# EMP31.net
KiCad netlist of a schematic drawn in EAGLE
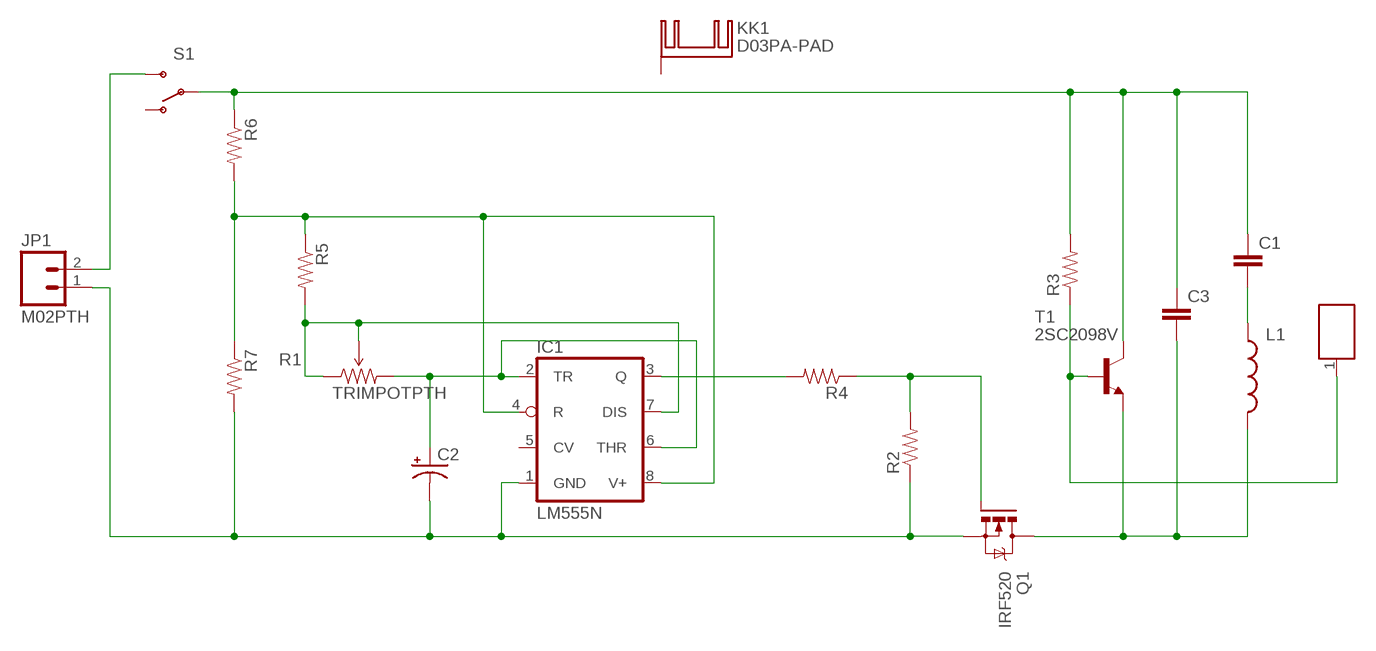
[diagram p0: schematic, sheet 1]

(export (version "E")
  (design (tool "Eeschema 10.0.6"))
  (components
    (comp (ref "C1")
      (value "CAPEZ")
      (footprint "eagle-import:CAP-PTH-SMALLEZ")
      (libsource (lib "eagle-import") (part "CAPEZ"))
    )
    (comp (ref "C2")
      (value "CAP_POLPTH2")
      (footprint "eagle-import:CPOL-RADIAL-10UF-25V")
      (libsource (lib "eagle-import") (part "CAP_POLPTH2"))
    )
    (comp (ref "C3")
      (value "CAPEZ")
      (footprint "eagle-import:CAP-PTH-SMALLEZ")
      (libsource (lib "eagle-import") (part "CAPEZ"))
    )
    (comp (ref "IC1")
      (value "LM555N")
      (footprint "eagle-import:DIL08-ROUND")
      (libsource (lib "eagle-import") (part "555NLM"))
    )
    (comp (ref "JP1")
      (value "M02PTH")
      (footprint "eagle-import:1X02")
      (libsource (lib "eagle-import") (part "M02PTH"))
    )
    (comp (ref "KK1")
      (value "D03PA-PAD")
      (footprint "eagle-import:D03PA-PAD")
      (libsource (lib "eagle-import") (part "D03PA-PAD"))
    )
    (comp (ref "L1")
      (value "INDUCTORCR54-KIT")
      (footprint "eagle-import:CR54-KIT")
      (libsource (lib "eagle-import") (part "INDUCTORCR54-KIT"))
    )
    (comp (ref "Q1")
      (value "IRF520")
      (footprint "eagle-import:TO220BV")
      (libsource (lib "eagle-import") (part "IRF520"))
    )
    (comp (ref "R1")
      (value "TRIMPOTPTH")
      (footprint "eagle-import:TRIM_POT_PTH")
      (libsource (lib "eagle-import") (part "TRIMPOTPTH"))
    )
    (comp (ref "R2")
      (value "RESISTOREZ")
      (footprint "eagle-import:AXIAL-0.3EZ")
      (libsource (lib "eagle-import") (part "RESISTOREZ"))
    )
    (comp (ref "R3")
      (value "RESISTOREZ")
      (footprint "eagle-import:AXIAL-0.3EZ")
      (libsource (lib "eagle-import") (part "RESISTOREZ"))
    )
    (comp (ref "R4")
      (value "RESISTOREZ")
      (footprint "eagle-import:AXIAL-0.3EZ")
      (libsource (lib "eagle-import") (part "RESISTOREZ"))
    )
    (comp (ref "R5")
      (value "RESISTOREZ")
      (footprint "eagle-import:AXIAL-0.3EZ")
      (libsource (lib "eagle-import") (part "RESISTOREZ"))
    )
    (comp (ref "R6")
      (value "RESISTOREZ")
      (footprint "eagle-import:AXIAL-0.3EZ")
      (libsource (lib "eagle-import") (part "RESISTOREZ"))
    )
    (comp (ref "R7")
      (value "RESISTOREZ")
      (footprint "eagle-import:AXIAL-0.3EZ")
      (libsource (lib "eagle-import") (part "RESISTOREZ"))
    )
    (comp (ref "S1")
      (value "SWITCH-SPDTPTH")
      (footprint "eagle-import:SWITCH-SPDT")
      (libsource (lib "eagle-import") (part "SWITCH-SPDTPTH"))
    )
    (comp (ref "T1")
      (value "2SC2098V")
      (footprint "eagle-import:TO220AV")
      (libsource (lib "eagle-import") (part "2SC2098V"))
    )
    (comp (ref "U$1")
      (value "L2_JOB37")
      (footprint "eagle-import:L2_JOB37")
      (libsource (lib "eagle-import") (part "L2_JOB37"))
    )
  )
  (nets
    (net (code "1") (name "Net-(C2-+)") (class "Default")
      (node (ref "C2") (pin "1") (pinfunction "+_1") (pintype "passive"))
      (node (ref "IC1") (pin "2") (pinfunction "TR_2") (pintype "input"))
      (node (ref "IC1") (pin "6") (pinfunction "THR_6") (pintype "input"))
      (node (ref "R1") (pin "3") (pinfunction "CW_3") (pintype "passive"))
    )
    (net (code "2") (name "Net-(C2--)") (class "Default")
      (node (ref "C2") (pin "2") (pinfunction "-_2") (pintype "passive"))
      (node (ref "IC1") (pin "1") (pinfunction "GND_1") (pintype "power_in"))
      (node (ref "JP1") (pin "1") (pinfunction "1_1") (pintype "passive"))
      (node (ref "Q1") (pin "S") (pinfunction "S_S") (pintype "passive"))
      (node (ref "R2") (pin "P$1") (pinfunction "1_P$1") (pintype "passive"))
      (node (ref "R7") (pin "P$2") (pinfunction "2_P$2") (pintype "passive"))
    )
    (net (code "3") (name "Net-(IC1-DIS)") (class "Default")
      (node (ref "IC1") (pin "7") (pinfunction "DIS_7") (pintype "input"))
      (node (ref "R1") (pin "1") (pinfunction "CCW_1") (pintype "passive"))
      (node (ref "R1") (pin "2") (pinfunction "WIPER_2") (pintype "passive"))
      (node (ref "R5") (pin "P$2") (pinfunction "2_P$2") (pintype "passive"))
    )
    (net (code "4") (name "Net-(IC1-Q)") (class "Default")
      (node (ref "IC1") (pin "3") (pinfunction "Q_3") (pintype "output"))
      (node (ref "R4") (pin "P$2") (pinfunction "2_P$2") (pintype "passive"))
    )
    (net (code "5") (name "Net-(IC1-R)") (class "Default")
      (node (ref "IC1") (pin "4") (pinfunction "R_4") (pintype "input"))
      (node (ref "IC1") (pin "8") (pinfunction "V+_8") (pintype "power_in"))
      (node (ref "R5") (pin "P$1") (pinfunction "1_P$1") (pintype "passive"))
      (node (ref "R6") (pin "P$2") (pinfunction "2_P$2") (pintype "passive"))
      (node (ref "R7") (pin "P$1") (pinfunction "1_P$1") (pintype "passive"))
    )
    (net (code "6") (name "Net-(L1-1)") (class "Default")
      (node (ref "C1") (pin "2") (pinfunction "2_2") (pintype "passive"))
      (node (ref "L1") (pin "P$1") (pinfunction "1_P$1") (pintype "passive"))
    )
    (net (code "7") (name "Net-(L1-2)") (class "Default")
      (node (ref "C3") (pin "2") (pinfunction "2_2") (pintype "passive"))
      (node (ref "L1") (pin "P$2") (pinfunction "2_P$2") (pintype "passive"))
      (node (ref "Q1") (pin "D") (pinfunction "D_D") (pintype "passive"))
      (node (ref "T1") (pin "3") (pinfunction "E_3") (pintype "passive"))
    )
    (net (code "8") (name "Net-(R2-2)") (class "Default")
      (node (ref "Q1") (pin "G") (pinfunction "G_G") (pintype "passive"))
      (node (ref "R2") (pin "P$2") (pinfunction "2_P$2") (pintype "passive"))
      (node (ref "R4") (pin "P$1") (pinfunction "1_P$1") (pintype "passive"))
    )
    (net (code "9") (name "Net-(R3-1)") (class "Default")
      (node (ref "R3") (pin "P$1") (pinfunction "1_P$1") (pintype "passive"))
      (node (ref "T1") (pin "1") (pinfunction "B_1") (pintype "passive"))
      (node (ref "U$1") (pin "1") (pinfunction "1_1") (pintype "bidirectional"))
    )
    (net (code "10") (name "Net-(R3-2)") (class "Default")
      (node (ref "C1") (pin "1") (pinfunction "1_1") (pintype "passive"))
      (node (ref "C3") (pin "1") (pinfunction "1_1") (pintype "passive"))
      (node (ref "R3") (pin "P$2") (pinfunction "2_P$2") (pintype "passive"))
      (node (ref "R6") (pin "P$1") (pinfunction "1_P$1") (pintype "passive"))
      (node (ref "S1") (pin "2") (pinfunction "P_2") (pintype "passive"))
      (node (ref "T1") (pin "2") (pinfunction "C_2") (pintype "passive"))
    )
    (net (code "11") (name "Net-(S1-S)") (class "Default")
      (node (ref "JP1") (pin "2") (pinfunction "2_2") (pintype "passive"))
      (node (ref "S1") (pin "3") (pinfunction "S_3") (pintype "passive"))
    )
    (net (code "12") (name "unconnected-(IC1-CV-Pad5)") (class "Default")
      (node (ref "IC1") (pin "5") (pinfunction "CV_5") (pintype "input"))
    )
    (net (code "13") (name "unconnected-(KK1-K-PadB)") (class "Default")
      (node (ref "KK1") (pin "B") (pinfunction "K_B") (pintype "passive"))
    )
    (net (code "14") (name "unconnected-(S1-O-Pad1)") (class "Default")
      (node (ref "S1") (pin "1") (pinfunction "O_1") (pintype "passive"))
    )
  )
)
